# CMoy-Pro-V_2_0_0_0a.net
KiCad netlist of a schematic drawn in EAGLE
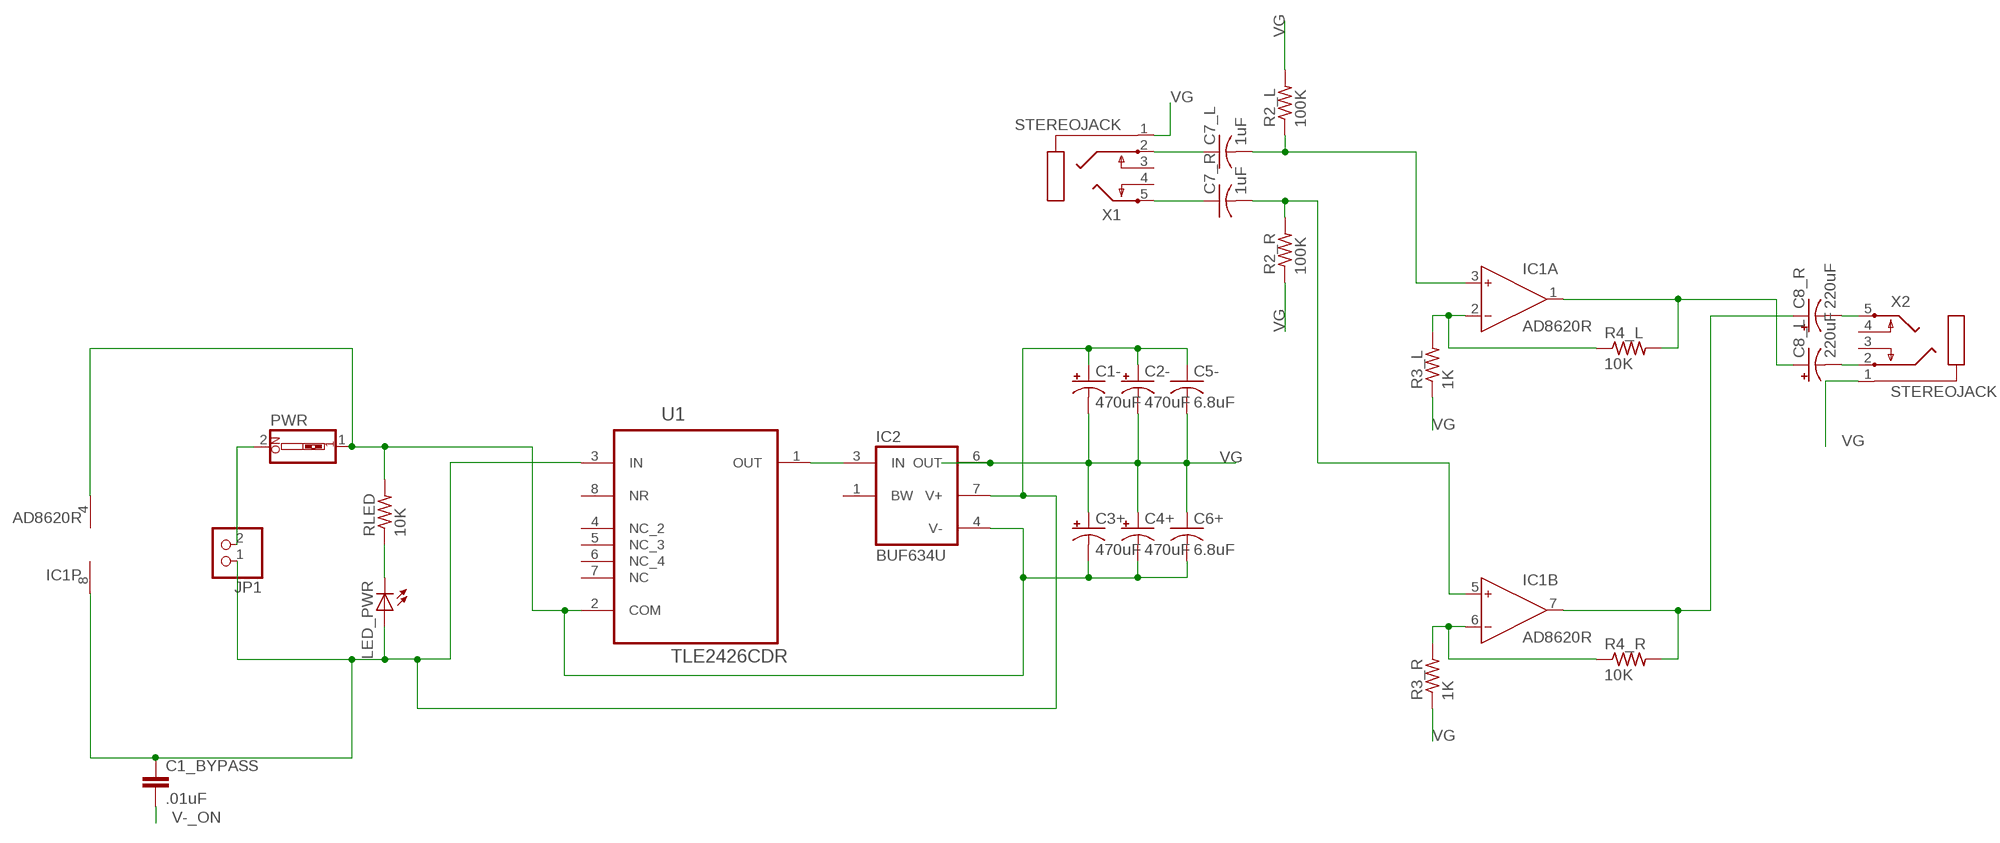
[diagram p0: schematic, sheet 1]

(export (version "E")
  (design (tool "Eeschema 10.0.6"))
  (components
    (comp (ref "C1-")
      (value "470uF")
      (footprint "eagle-import:E3,5-10")
      (libsource (lib "eagle-import") (part "CPOL-USE3.5-10"))
    )
    (comp (ref "C1_BYPASS")
      (value ".01uF")
      (footprint "eagle-import:C0402")
      (libsource (lib "eagle-import") (part "C-EUC0402"))
    )
    (comp (ref "C2-")
      (value "470uF")
      (footprint "eagle-import:E3,5-10")
      (libsource (lib "eagle-import") (part "CPOL-USE3.5-10"))
    )
    (comp (ref "C3+")
      (value "470uF")
      (footprint "eagle-import:E3,5-10")
      (libsource (lib "eagle-import") (part "CPOL-USE3.5-10"))
    )
    (comp (ref "C4+")
      (value "470uF")
      (footprint "eagle-import:E3,5-10")
      (libsource (lib "eagle-import") (part "CPOL-USE3.5-10"))
    )
    (comp (ref "C5-")
      (value "6.8uF")
      (footprint "eagle-import:C075-042X103")
      (libsource (lib "eagle-import") (part "C-US075-042X103"))
    )
    (comp (ref "C6+")
      (value "6.8uF")
      (footprint "eagle-import:C075-042X103")
      (libsource (lib "eagle-import") (part "C-US075-042X103"))
    )
    (comp (ref "C7_L")
      (value "1uF")
      (footprint "eagle-import:C075-042X103")
      (libsource (lib "eagle-import") (part "C-US075-042X103"))
    )
    (comp (ref "C7_R")
      (value "1uF")
      (footprint "eagle-import:C075-042X103")
      (libsource (lib "eagle-import") (part "C-US075-042X103"))
    )
    (comp (ref "C8_L")
      (value "220uF")
      (footprint "eagle-import:E3,5-10")
      (libsource (lib "eagle-import") (part "CPOL-USE3.5-10"))
    )
    (comp (ref "C8_R")
      (value "220uF")
      (footprint "eagle-import:E3,5-10")
      (libsource (lib "eagle-import") (part "CPOL-USE3.5-10"))
    )
    (comp (ref "IC1")
      (value "AD8620R")
      (footprint "eagle-import:SO8")
      (fields (field (name "MF") "ALTERA CORPORATION") (field (name "MPN") "AD8620ARZ"))
      (libsource (lib "eagle-import") (part "AD8620R"))
    )
    (comp (ref "IC2")
      (value "BUF634U")
      (footprint "eagle-import:SO08")
      (fields (field (name "MF") "TEXAS INSTRUMENTS"))
      (libsource (lib "eagle-import") (part "BUF634U"))
    )
    (comp (ref "JP1")
      (value "PINHD-1X2")
      (footprint "eagle-import:1X02")
      (libsource (lib "eagle-import") (part "PINHD-1X2"))
    )
    (comp (ref "LED_PWR")
      (value "LED3MM")
      (footprint "eagle-import:LED3MM")
      (libsource (lib "eagle-import") (part "LED3MM"))
    )
    (comp (ref "PWR")
      (value "SW_DIP-1")
      (footprint "eagle-import:EDG-01")
      (libsource (lib "eagle-import") (part "SW_DIP-1"))
    )
    (comp (ref "R2_L")
      (value "100K")
      (footprint "eagle-import:0207_7")
      (libsource (lib "eagle-import") (part "R-US_0207/7"))
    )
    (comp (ref "R2_R")
      (value "100K")
      (footprint "eagle-import:0207_7")
      (libsource (lib "eagle-import") (part "R-US_0207/7"))
    )
    (comp (ref "R3_L")
      (value "1K")
      (footprint "eagle-import:0207_7")
      (libsource (lib "eagle-import") (part "R-US_0207/7"))
    )
    (comp (ref "R3_R")
      (value "1K")
      (footprint "eagle-import:0207_7")
      (libsource (lib "eagle-import") (part "R-US_0207/7"))
    )
    (comp (ref "R4_L")
      (value "10K")
      (footprint "eagle-import:0207_7")
      (libsource (lib "eagle-import") (part "R-US_0207/7"))
    )
    (comp (ref "R4_R")
      (value "10K")
      (footprint "eagle-import:0207_7")
      (libsource (lib "eagle-import") (part "R-US_0207/7"))
    )
    (comp (ref "RLED")
      (value "10K")
      (footprint "eagle-import:0207_7")
      (libsource (lib "eagle-import") (part "R-US_0207/7"))
    )
    (comp (ref "U1")
      (value "TLE2426CDR")
      (footprint "eagle-import:SOIC127P600X175-8N")
      (libsource (lib "eagle-import") (part "TLE2426CDR"))
    )
    (comp (ref "X1")
      (value "STEREOJACK")
      (footprint "eagle-import:STX3100")
      (libsource (lib "eagle-import") (part "STEREOJACK"))
    )
    (comp (ref "X2")
      (value "STEREOJACK")
      (footprint "eagle-import:STX3100")
      (libsource (lib "eagle-import") (part "STEREOJACK"))
    )
  )
  (nets
    (net (code "1") (name "/V-_ON") (class "Default")
      (node (ref "C1_BYPASS") (pin "2") (pinfunction "2_2") (pintype "passive"))
      (node (ref "C3+") (pin "-") (pinfunction "-_-") (pintype "passive"))
      (node (ref "C4+") (pin "-") (pinfunction "-_-") (pintype "passive"))
      (node (ref "C6+") (pin "2") (pinfunction "2_2") (pintype "passive"))
      (node (ref "IC1") (pin "4") (pinfunction "V-_4") (pintype "power_in"))
      (node (ref "IC2") (pin "4") (pinfunction "V-_4") (pintype "power_in"))
      (node (ref "PWR") (pin "1") (pinfunction "1_1") (pintype "passive"))
      (node (ref "RLED") (pin "2") (pinfunction "2_2") (pintype "passive"))
      (node (ref "U1") (pin "2") (pinfunction "COM_2") (pintype "passive"))
    )
    (net (code "2") (name "/VG") (class "Default")
      (node (ref "C1-") (pin "-") (pinfunction "-_-") (pintype "passive"))
      (node (ref "C2-") (pin "-") (pinfunction "-_-") (pintype "passive"))
      (node (ref "C3+") (pin "+") (pinfunction "+_+") (pintype "passive"))
      (node (ref "C4+") (pin "+") (pinfunction "+_+") (pintype "passive"))
      (node (ref "C5-") (pin "2") (pinfunction "2_2") (pintype "passive"))
      (node (ref "C6+") (pin "1") (pinfunction "1_1") (pintype "passive"))
      (node (ref "IC2") (pin "6") (pinfunction "OUT_6") (pintype "output"))
      (node (ref "R2_L") (pin "2") (pinfunction "2_2") (pintype "passive"))
      (node (ref "R2_R") (pin "1") (pinfunction "1_1") (pintype "passive"))
      (node (ref "R3_L") (pin "1") (pinfunction "1_1") (pintype "passive"))
      (node (ref "R3_R") (pin "1") (pinfunction "1_1") (pintype "passive"))
      (node (ref "X1") (pin "1") (pinfunction "1_1") (pintype "passive"))
      (node (ref "X2") (pin "1") (pinfunction "1_1") (pintype "passive"))
    )
    (net (code "3") (name "Net-(C7_L-Pad1)") (class "Default")
      (node (ref "C7_L") (pin "1") (pinfunction "1_1") (pintype "passive"))
      (node (ref "X1") (pin "2") (pinfunction "2_2") (pintype "passive"))
    )
    (net (code "4") (name "Net-(C7_R-Pad1)") (class "Default")
      (node (ref "C7_R") (pin "1") (pinfunction "1_1") (pintype "passive"))
      (node (ref "X1") (pin "5") (pinfunction "5_5") (pintype "passive"))
    )
    (net (code "5") (name "Net-(C8_L-Pad-)") (class "Default")
      (node (ref "C8_L") (pin "-") (pinfunction "-_-") (pintype "passive"))
      (node (ref "X2") (pin "2") (pinfunction "2_2") (pintype "passive"))
    )
    (net (code "6") (name "Net-(C8_R-Pad-)") (class "Default")
      (node (ref "C8_R") (pin "-") (pinfunction "-_-") (pintype "passive"))
      (node (ref "X2") (pin "5") (pinfunction "5_5") (pintype "passive"))
    )
    (net (code "7") (name "Net-(IC1A-IN+)") (class "Default")
      (node (ref "C7_L") (pin "2") (pinfunction "2_2") (pintype "passive"))
      (node (ref "IC1") (pin "3") (pinfunction "IN+_3") (pintype "input"))
      (node (ref "R2_L") (pin "1") (pinfunction "1_1") (pintype "passive"))
    )
    (net (code "8") (name "Net-(IC1A-IN-)") (class "Default")
      (node (ref "IC1") (pin "2") (pinfunction "IN-_2") (pintype "input"))
      (node (ref "R3_L") (pin "2") (pinfunction "2_2") (pintype "passive"))
      (node (ref "R4_L") (pin "1") (pinfunction "1_1") (pintype "passive"))
    )
    (net (code "9") (name "Net-(IC1A-OUT)") (class "Default")
      (node (ref "C8_L") (pin "+") (pinfunction "+_+") (pintype "passive"))
      (node (ref "IC1") (pin "1") (pinfunction "OUT_1") (pintype "output"))
      (node (ref "R4_L") (pin "2") (pinfunction "2_2") (pintype "passive"))
    )
    (net (code "10") (name "Net-(IC1B-IN+)") (class "Default")
      (node (ref "C7_R") (pin "2") (pinfunction "2_2") (pintype "passive"))
      (node (ref "IC1") (pin "5") (pinfunction "IN+_5") (pintype "input"))
      (node (ref "R2_R") (pin "2") (pinfunction "2_2") (pintype "passive"))
    )
    (net (code "11") (name "Net-(IC1B-IN-)") (class "Default")
      (node (ref "IC1") (pin "6") (pinfunction "IN-_6") (pintype "input"))
      (node (ref "R3_R") (pin "2") (pinfunction "2_2") (pintype "passive"))
      (node (ref "R4_R") (pin "1") (pinfunction "1_1") (pintype "passive"))
    )
    (net (code "12") (name "Net-(IC1B-OUT)") (class "Default")
      (node (ref "C8_R") (pin "+") (pinfunction "+_+") (pintype "passive"))
      (node (ref "IC1") (pin "7") (pinfunction "OUT_7") (pintype "output"))
      (node (ref "R4_R") (pin "2") (pinfunction "2_2") (pintype "passive"))
    )
    (net (code "13") (name "Net-(IC1C-V+)") (class "Default")
      (node (ref "C1-") (pin "+") (pinfunction "+_+") (pintype "passive"))
      (node (ref "C1_BYPASS") (pin "1") (pinfunction "1_1") (pintype "passive"))
      (node (ref "C2-") (pin "+") (pinfunction "+_+") (pintype "passive"))
      (node (ref "C5-") (pin "1") (pinfunction "1_1") (pintype "passive"))
      (node (ref "IC1") (pin "8") (pinfunction "V+_8") (pintype "power_in"))
      (node (ref "IC2") (pin "7") (pinfunction "V+_7") (pintype "power_in"))
      (node (ref "JP1") (pin "1") (pinfunction "1_1") (pintype "passive"))
      (node (ref "LED_PWR") (pin "A") (pinfunction "A_A") (pintype "passive"))
      (node (ref "U1") (pin "3") (pinfunction "IN_3") (pintype "power_in"))
    )
    (net (code "14") (name "Net-(IC2-IN)") (class "Default")
      (node (ref "IC2") (pin "3") (pinfunction "IN_3") (pintype "input"))
      (node (ref "U1") (pin "1") (pinfunction "OUT_1") (pintype "output"))
    )
    (net (code "15") (name "Net-(JP1-Pad2)") (class "Default")
      (node (ref "JP1") (pin "2") (pinfunction "2_2") (pintype "passive"))
      (node (ref "PWR") (pin "2") (pinfunction "2_2") (pintype "passive"))
    )
    (net (code "16") (name "Net-(LED_PWR-C)") (class "Default")
      (node (ref "LED_PWR") (pin "K") (pinfunction "C_K") (pintype "passive"))
      (node (ref "RLED") (pin "1") (pinfunction "1_1") (pintype "passive"))
    )
    (net (code "17") (name "unconnected-(IC2-BW-Pad1)") (class "Default")
      (node (ref "IC2") (pin "1") (pinfunction "BW_1") (pintype "passive"))
    )
    (net (code "18") (name "unconnected-(U1-NC-Pad7)") (class "Default")
      (node (ref "U1") (pin "7") (pinfunction "NC_7") (pintype "no_connect"))
    )
    (net (code "19") (name "unconnected-(U1-NC_2-Pad4)") (class "Default")
      (node (ref "U1") (pin "4") (pinfunction "NC_2_4") (pintype "no_connect"))
    )
    (net (code "20") (name "unconnected-(U1-NC_3-Pad5)") (class "Default")
      (node (ref "U1") (pin "5") (pinfunction "NC_3_5") (pintype "no_connect"))
    )
    (net (code "21") (name "unconnected-(U1-NC_4-Pad6)") (class "Default")
      (node (ref "U1") (pin "6") (pinfunction "NC_4_6") (pintype "no_connect"))
    )
    (net (code "22") (name "unconnected-(U1-NR-Pad8)") (class "Default")
      (node (ref "U1") (pin "8") (pinfunction "NR_8") (pintype "passive"))
    )
    (net (code "23") (name "unconnected-(X1-Pad3)") (class "Default")
      (node (ref "X1") (pin "3") (pinfunction "3_3") (pintype "passive"))
    )
    (net (code "24") (name "unconnected-(X1-Pad4)") (class "Default")
      (node (ref "X1") (pin "4") (pinfunction "4_4") (pintype "passive"))
    )
    (net (code "25") (name "unconnected-(X2-Pad3)") (class "Default")
      (node (ref "X2") (pin "3") (pinfunction "3_3") (pintype "passive"))
    )
    (net (code "26") (name "unconnected-(X2-Pad4)") (class "Default")
      (node (ref "X2") (pin "4") (pinfunction "4_4") (pintype "passive"))
    )
  )
)
